# MCUConfig.net
KiCad netlist of a schematic drawn in Altium Designer
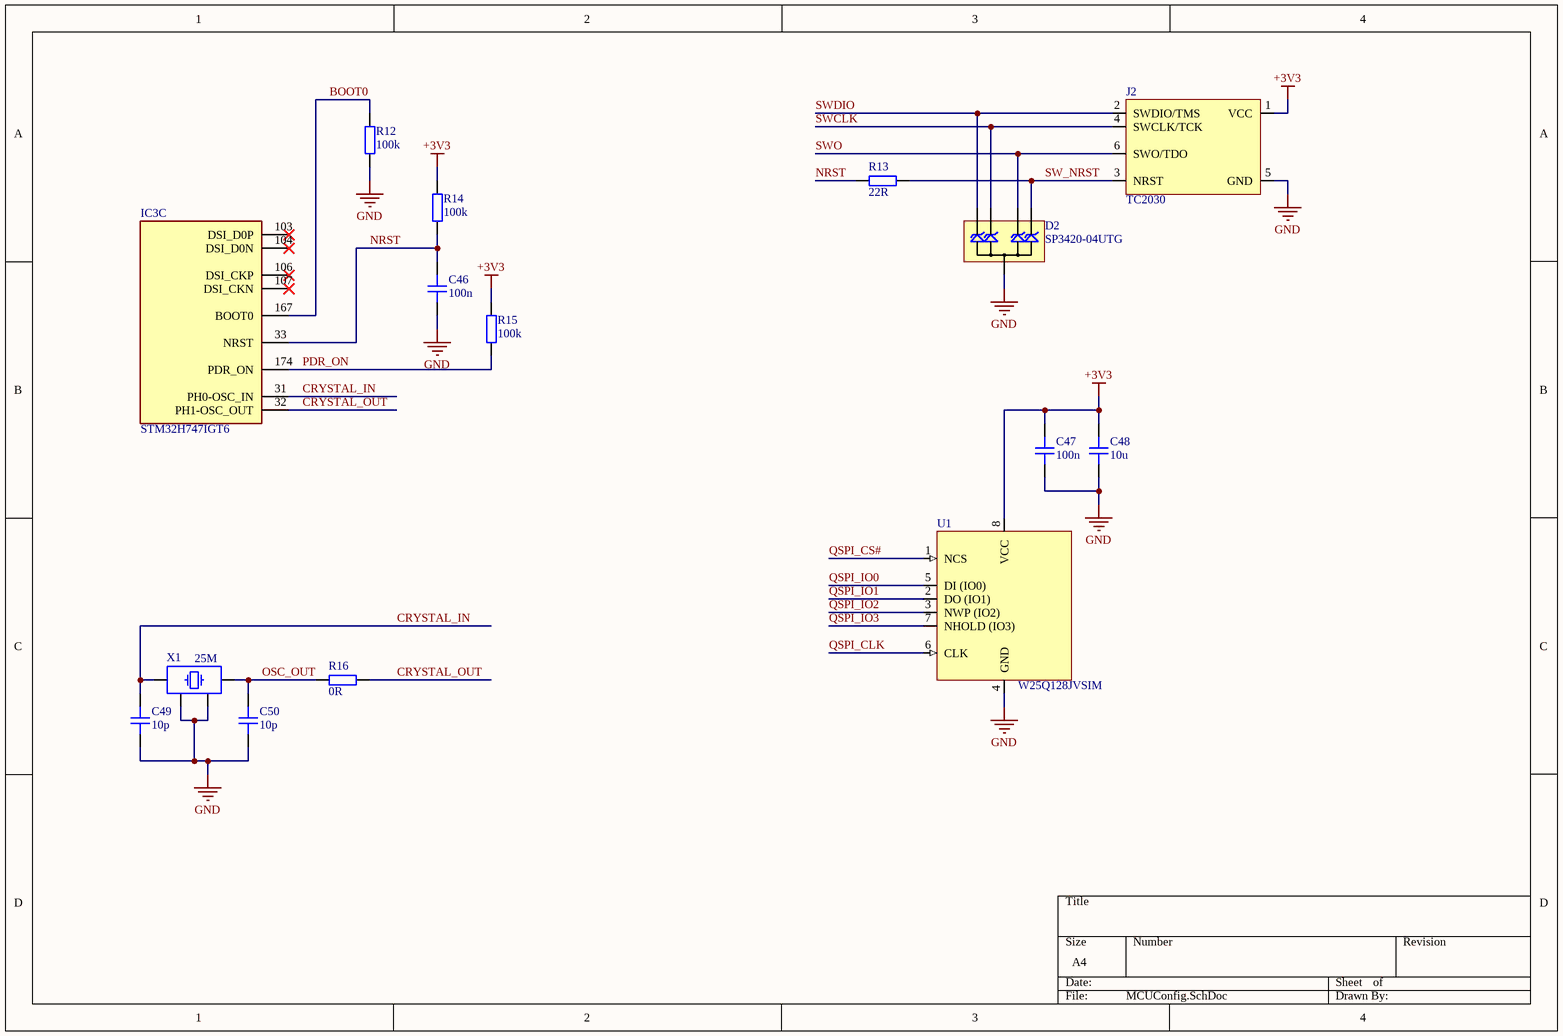
[diagram p0: MCUConfig.SchDoc]

(export (version "E")
  (design (tool "Eeschema 10.0.6"))
  (components
    (comp (ref "C46")
      (value "100n")
      (footprint "CAP_0402")
      (description "Capacitor SMD 0402")
      (libsource (lib "Schematic-Lib-PhilsLab") (part "CAP_0402"))
    )
    (comp (ref "C47")
      (value "100n")
      (footprint "CAP_0402")
      (description "Capacitor SMD 0402")
      (libsource (lib "Schematic-Lib-PhilsLab") (part "CAP_0402"))
    )
    (comp (ref "C48")
      (value "10u")
      (footprint "CAP_0603")
      (description "Capacitor SMD 0603")
      (libsource (lib "Schematic-Lib-PhilsLab") (part "CAP_0603"))
    )
    (comp (ref "C49")
      (value "10p")
      (footprint "CAP_0402")
      (description "Capacitor SMD 0402")
      (libsource (lib "Schematic-Lib-PhilsLab") (part "CAP_0402"))
    )
    (comp (ref "C50")
      (value "10p")
      (footprint "CAP_0402")
      (description "Capacitor SMD 0402")
      (libsource (lib "Schematic-Lib-PhilsLab") (part "CAP_0402"))
    )
    (comp (ref "D2")
      (value "SP3420-04UTG")
      (footprint "uDFN-10")
      (description "TVS Diode Array Low Capacitance ESD Protection 4-Channel (Vwork=3V3, Vclamp=6V)")
      (fields (field (name "MANUFACTURER") "Littelfuse"))
      (libsource (lib "Schematic-Lib-PhilsLab") (part "SP3420-04UTG"))
    )
    (comp (ref "IC3")
      (value "STM32H747IGT6")
      (footprint "Footprint-Lib-PhilsLab:QFP50P2600X2600X160-176N")
      (description "Integrated Circuit")
      (fields (field (name "MOUSER PART NUMBER") "511-STM32H747IGT6"))
      (libsource (lib "Schematic-Lib-PhilsLab") (part "STM32H747IGT6"))
    )
    (comp (ref "J2")
      (value "TC2030")
      (footprint "TC2030-FP")
      (description "Tag-Connect No-Solder SWD Debug Connector DO NOT PLACE")
      (fields (field (name "MANUFACTURER") "Tag-Connect"))
      (libsource (lib "Schematic-Lib-PhilsLab") (part "TC2030"))
    )
    (comp (ref "R12")
      (value "100k")
      (footprint "RES_0402")
      (description "Resistor SMD 0402")
      (libsource (lib "Schematic-Lib-PhilsLab") (part "RES_0402"))
    )
    (comp (ref "R13")
      (value "22R")
      (footprint "RES_0402")
      (description "Resistor SMD 0402")
      (libsource (lib "Schematic-Lib-PhilsLab") (part "RES_0402"))
    )
    (comp (ref "R14")
      (value "100k")
      (footprint "RES_0402")
      (description "Resistor SMD 0402")
      (libsource (lib "Schematic-Lib-PhilsLab") (part "RES_0402"))
    )
    (comp (ref "R15")
      (value "100k")
      (footprint "RES_0402")
      (description "Resistor SMD 0402")
      (libsource (lib "Schematic-Lib-PhilsLab") (part "RES_0402"))
    )
    (comp (ref "R16")
      (value "0R")
      (footprint "RES_0402")
      (description "Resistor SMD 0402")
      (libsource (lib "Schematic-Lib-PhilsLab") (part "RES_0402"))
    )
    (comp (ref "U1")
      (value "W25Q128JVSIM")
      (footprint "SOIC-8")
      (description "128M-BIT\r\nSERIAL FLASH MEMORY WITH\r\nDUAL/QUAD SPI & QPI & DTR SOIC-8")
      (fields (field (name "MANUFACTURER") "Winbond"))
      (libsource (lib "Schematic-Lib-PhilsLab") (part "W25Q128JVSIM"))
    )
    (comp (ref "X1")
      (value "25M")
      (footprint "XTAL_3225")
      (description "Crystal SMD 3225")
      (libsource (lib "Schematic-Lib-PhilsLab") (part "XTAL_3225"))
    )
  )
  (nets
    (net (code "1") (name "+3V3") (class "Default")
      (node (ref "C47") (pin "2") (pinfunction "2_2") (pintype "passive"))
      (node (ref "C48") (pin "2") (pinfunction "2_2") (pintype "passive"))
      (node (ref "J2") (pin "1") (pinfunction "VCC_1") (pintype "passive"))
      (node (ref "R14") (pin "2") (pinfunction "2_2") (pintype "passive"))
      (node (ref "R15") (pin "2") (pinfunction "2_2") (pintype "passive"))
      (node (ref "U1") (pin "8") (pinfunction "VCC_8") (pintype "power_in"))
    )
    (net (code "2") (name "/BOOT0") (class "Default")
      (node (ref "IC3") (pin "167") (pinfunction "BOOT0_167") (pintype "passive"))
      (node (ref "R12") (pin "2") (pinfunction "2_2") (pintype "passive"))
    )
    (net (code "3") (name "/CRYSTAL_IN") (class "Default")
      (node (ref "C49") (pin "2") (pinfunction "2_2") (pintype "passive"))
      (node (ref "IC3") (pin "31") (pinfunction "PH0-OSC_IN_31") (pintype "passive"))
      (node (ref "X1") (pin "1") (pinfunction "1_1") (pintype "passive"))
    )
    (net (code "4") (name "/CRYSTAL_OUT") (class "Default")
      (node (ref "IC3") (pin "32") (pinfunction "PH1-OSC_OUT_32") (pintype "passive"))
      (node (ref "R16") (pin "2") (pinfunction "2_2") (pintype "passive"))
    )
    (net (code "5") (name "/NRST") (class "Default")
      (node (ref "C46") (pin "2") (pinfunction "2_2") (pintype "passive"))
      (node (ref "IC3") (pin "33") (pinfunction "NRST_33") (pintype "passive"))
      (node (ref "R13") (pin "2") (pinfunction "2_2") (pintype "passive"))
      (node (ref "R14") (pin "1") (pinfunction "1_1") (pintype "passive"))
    )
    (net (code "6") (name "/OSC_OUT") (class "Default")
      (node (ref "C50") (pin "2") (pinfunction "2_2") (pintype "passive"))
      (node (ref "R16") (pin "1") (pinfunction "1_1") (pintype "passive"))
      (node (ref "X1") (pin "3") (pinfunction "3_3") (pintype "passive"))
    )
    (net (code "7") (name "/PDR_ON") (class "Default")
      (node (ref "IC3") (pin "174") (pinfunction "PDR_ON_174") (pintype "passive"))
      (node (ref "R15") (pin "1") (pinfunction "1_1") (pintype "passive"))
    )
    (net (code "8") (name "/QSPI_CLK") (class "Default")
      (node (ref "U1") (pin "6") (pinfunction "CLK_6") (pintype "input"))
    )
    (net (code "9") (name "/QSPI_CS#") (class "Default")
      (node (ref "U1") (pin "1") (pinfunction "NCS_1") (pintype "input"))
    )
    (net (code "10") (name "/QSPI_IO0") (class "Default")
      (node (ref "U1") (pin "5") (pinfunction "DI_(IO0)_5") (pintype "bidirectional"))
    )
    (net (code "11") (name "/QSPI_IO1") (class "Default")
      (node (ref "U1") (pin "2") (pinfunction "DO_(IO1)_2") (pintype "bidirectional"))
    )
    (net (code "12") (name "/QSPI_IO2") (class "Default")
      (node (ref "U1") (pin "3") (pinfunction "NWP_(IO2)_3") (pintype "bidirectional"))
    )
    (net (code "13") (name "/QSPI_IO3") (class "Default")
      (node (ref "U1") (pin "7") (pinfunction "NHOLD_(IO3)_7") (pintype "bidirectional"))
    )
    (net (code "14") (name "/SWCLK") (class "Default")
      (node (ref "D2") (pin "29") (pintype "passive"))
      (node (ref "J2") (pin "4") (pinfunction "SWCLK/TCK_4") (pintype "passive"))
    )
    (net (code "15") (name "/SWDIO") (class "Default")
      (node (ref "D2") (pin "110") (pintype "passive"))
      (node (ref "J2") (pin "2") (pinfunction "SWDIO/TMS_2") (pintype "passive"))
    )
    (net (code "16") (name "/SWO") (class "Default")
      (node (ref "D2") (pin "47") (pintype "passive"))
      (node (ref "J2") (pin "6") (pinfunction "SWO/TDO_6") (pintype "passive"))
    )
    (net (code "17") (name "/SW_NRST") (class "Default")
      (node (ref "D2") (pin "56") (pintype "passive"))
      (node (ref "J2") (pin "3") (pinfunction "NRST_3") (pintype "passive"))
      (node (ref "R13") (pin "1") (pinfunction "1_1") (pintype "passive"))
    )
    (net (code "18") (name "GND") (class "Default")
      (node (ref "C46") (pin "1") (pinfunction "1_1") (pintype "passive"))
      (node (ref "C47") (pin "1") (pinfunction "1_1") (pintype "passive"))
      (node (ref "C48") (pin "1") (pinfunction "1_1") (pintype "passive"))
      (node (ref "C49") (pin "1") (pinfunction "1_1") (pintype "passive"))
      (node (ref "C50") (pin "1") (pinfunction "1_1") (pintype "passive"))
      (node (ref "D2") (pin "38") (pinfunction "GND_38") (pintype "passive"))
      (node (ref "J2") (pin "5") (pinfunction "GND_5") (pintype "passive"))
      (node (ref "R12") (pin "1") (pinfunction "1_1") (pintype "passive"))
      (node (ref "U1") (pin "4") (pinfunction "GND_4") (pintype "power_in"))
      (node (ref "X1") (pin "2") (pinfunction "2_2") (pintype "passive"))
      (node (ref "X1") (pin "4") (pinfunction "4_4") (pintype "passive"))
    )
    (net (code "19") (name "unconnected-(IC3C-DSI_CKN-Pad107)") (class "Default")
      (node (ref "IC3") (pin "107") (pinfunction "DSI_CKN_107") (pintype "passive+no_connect"))
    )
    (net (code "20") (name "unconnected-(IC3C-DSI_CKP-Pad106)") (class "Default")
      (node (ref "IC3") (pin "106") (pinfunction "DSI_CKP_106") (pintype "passive+no_connect"))
    )
    (net (code "21") (name "unconnected-(IC3C-DSI_D0N-Pad104)") (class "Default")
      (node (ref "IC3") (pin "104") (pinfunction "DSI_D0N_104") (pintype "passive+no_connect"))
    )
    (net (code "22") (name "unconnected-(IC3C-DSI_D0P-Pad103)") (class "Default")
      (node (ref "IC3") (pin "103") (pinfunction "DSI_D0P_103") (pintype "passive+no_connect"))
    )
  )
)
